# Granny_Safe_Microprocessor_Module.net
KiCad netlist of a schematic drawn in EAGLE
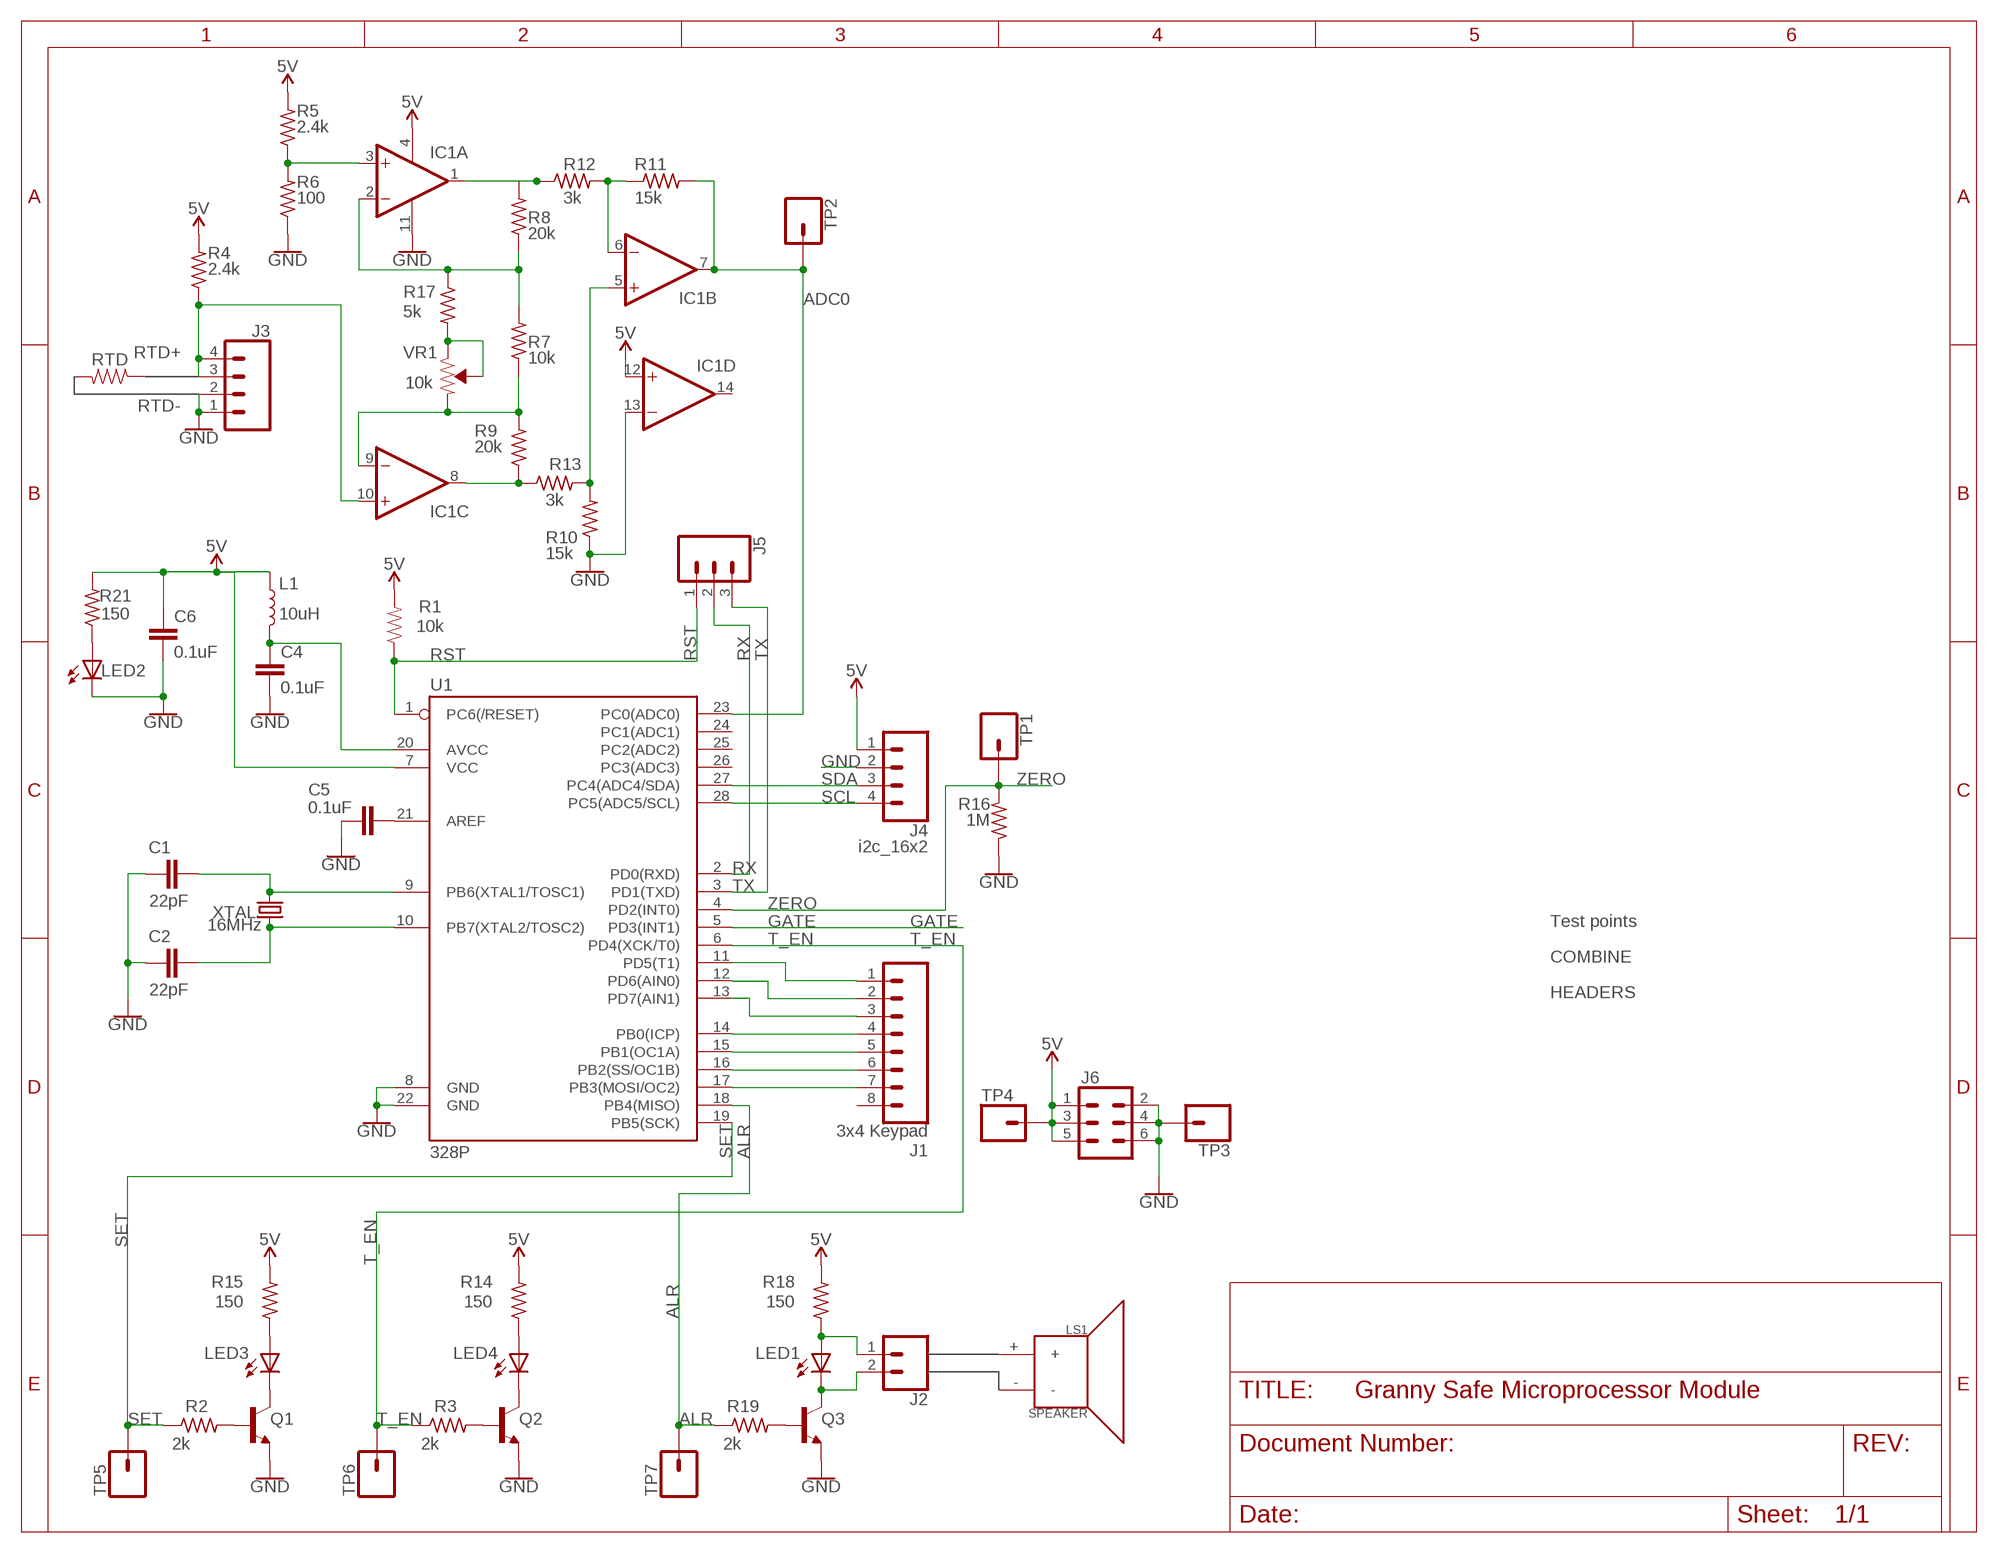
[diagram p0: schematic, sheet 1]

(export (version "E")
  (design (tool "Eeschema 10.0.6"))
  (components
    (comp (ref "C1")
      (value "22pF")
      (footprint "eagle-import:0603")
      (libsource (lib "eagle-import") (part "22PF-0603-50V-5%"))
    )
    (comp (ref "C2")
      (value "22pF")
      (footprint "eagle-import:0603")
      (libsource (lib "eagle-import") (part "22PF-0603-50V-5%"))
    )
    (comp (ref "C4")
      (value "0.1uF")
      (footprint "eagle-import:0603")
      (libsource (lib "eagle-import") (part "0.1UF-0603-25V-(+80/-20%)"))
    )
    (comp (ref "C5")
      (value "0.1uF")
      (footprint "eagle-import:0603")
      (libsource (lib "eagle-import") (part "0.1UF-0603-25V-(+80/-20%)"))
    )
    (comp (ref "C6")
      (value "0.1uF")
      (footprint "eagle-import:0603")
      (libsource (lib "eagle-import") (part "0.1UF-0603-25V-(+80/-20%)"))
    )
    (comp (ref "IC1")
      (value "MCP604SL")
      (footprint "eagle-import:SO14")
      (libsource (lib "eagle-import") (part "MCP604SL"))
    )
    (comp (ref "J1")
      (value "3x4 Keypad")
      (footprint "eagle-import:1X08")
      (libsource (lib "eagle-import") (part "CONN_08{dblquote}"))
    )
    (comp (ref "J2")
      (value "CONN_02")
      (footprint "eagle-import:1X02")
      (libsource (lib "eagle-import") (part "CONN_02"))
    )
    (comp (ref "J3")
      (value "SCREW-4")
      (footprint "eagle-import:SCREWTERMINAL-5MM-2")
      (libsource (lib "eagle-import") (part "SCREW-4"))
    )
    (comp (ref "J4")
      (value "i2c_16x2")
      (footprint "eagle-import:1X04")
      (libsource (lib "eagle-import") (part "CONN_04"))
    )
    (comp (ref "J5")
      (value "CONN_03")
      (footprint "eagle-import:1X03")
      (libsource (lib "eagle-import") (part "CONN_03"))
    )
    (comp (ref "J6")
      (value "FEMALE 2x3")
      (footprint "eagle-import:2X3")
      (libsource (lib "eagle-import") (part "CONN_03X2FEMALE"))
    )
    (comp (ref "L1")
      (value "10uH")
      (footprint "eagle-import:0603")
      (libsource (lib "eagle-import") (part "INDUCTOR-0603-33NH"))
    )
    (comp (ref "LED1")
      (value "LED5MM")
      (footprint "eagle-import:LED5MM")
      (libsource (lib "eagle-import") (part "LED5MM"))
    )
    (comp (ref "LED2")
      (value "LED5MM")
      (footprint "eagle-import:LED5MM")
      (libsource (lib "eagle-import") (part "LED5MM"))
    )
    (comp (ref "LED3")
      (value "LED5MM")
      (footprint "eagle-import:LED5MM")
      (libsource (lib "eagle-import") (part "LED5MM"))
    )
    (comp (ref "LED4")
      (value "LED5MM")
      (footprint "eagle-import:LED5MM")
      (libsource (lib "eagle-import") (part "LED5MM"))
    )
    (comp (ref "LS1")
      (value "SPEAKER")
      (footprint "eagle-import:PCB_MOUNT_SPEAKER")
      (libsource (lib "eagle-import") (part "SPEAKER"))
    )
    (comp (ref "Q1")
      (value "TRANS_NPN-MMBTA42")
      (footprint "eagle-import:SOT23-3")
      (libsource (lib "eagle-import") (part "TRANS_NPN-MMBTA42"))
    )
    (comp (ref "Q2")
      (value "TRANS_NPN-MMBTA42")
      (footprint "eagle-import:SOT23-3")
      (libsource (lib "eagle-import") (part "TRANS_NPN-MMBTA42"))
    )
    (comp (ref "Q3")
      (value "TRANS_NPN-MMBTA42")
      (footprint "eagle-import:SOT23-3")
      (libsource (lib "eagle-import") (part "TRANS_NPN-MMBTA42"))
    )
    (comp (ref "R1")
      (value "10k")
      (footprint "eagle-import:0603")
      (libsource (lib "eagle-import") (part "10KOHM-0603-1/10W-1%"))
    )
    (comp (ref "R2")
      (value "2k")
      (footprint "eagle-import:R0603")
      (libsource (lib "eagle-import") (part "R-US_R0603"))
    )
    (comp (ref "R3")
      (value "2k")
      (footprint "eagle-import:R0603")
      (libsource (lib "eagle-import") (part "R-US_R0603"))
    )
    (comp (ref "R4")
      (value "2.4k")
      (footprint "eagle-import:R0603")
      (libsource (lib "eagle-import") (part "resistor_348_R-US_R0603"))
    )
    (comp (ref "R5")
      (value "2.4k")
      (footprint "eagle-import:R0603")
      (libsource (lib "eagle-import") (part "resistor_348_R-US_R0603"))
    )
    (comp (ref "R6")
      (value "100")
      (footprint "eagle-import:R0603")
      (libsource (lib "eagle-import") (part "resistor_348_R-US_R0603"))
    )
    (comp (ref "R7")
      (value "10k")
      (footprint "eagle-import:R0603")
      (libsource (lib "eagle-import") (part "resistor_348_R-US_R0603"))
    )
    (comp (ref "R8")
      (value "20k")
      (footprint "eagle-import:R0603")
      (libsource (lib "eagle-import") (part "resistor_348_R-US_R0603"))
    )
    (comp (ref "R9")
      (value "20k")
      (footprint "eagle-import:R0603")
      (libsource (lib "eagle-import") (part "resistor_348_R-US_R0603"))
    )
    (comp (ref "R10")
      (value "15k")
      (footprint "eagle-import:R0603")
      (libsource (lib "eagle-import") (part "resistor_348_R-US_R0603"))
    )
    (comp (ref "R11")
      (value "15k")
      (footprint "eagle-import:R0603")
      (libsource (lib "eagle-import") (part "resistor_348_R-US_R0603"))
    )
    (comp (ref "R12")
      (value "3k")
      (footprint "eagle-import:R0603")
      (libsource (lib "eagle-import") (part "resistor_348_R-US_R0603"))
    )
    (comp (ref "R13")
      (value "3k")
      (footprint "eagle-import:R0603")
      (libsource (lib "eagle-import") (part "resistor_348_R-US_R0603"))
    )
    (comp (ref "R14")
      (value "150")
      (footprint "eagle-import:R0603")
      (libsource (lib "eagle-import") (part "R-US_R0603"))
    )
    (comp (ref "R15")
      (value "150")
      (footprint "eagle-import:R0603")
      (libsource (lib "eagle-import") (part "R-US_R0603"))
    )
    (comp (ref "R16")
      (value "1M")
      (footprint "eagle-import:R0603")
      (libsource (lib "eagle-import") (part "resistor_348_R-US_R0603"))
    )
    (comp (ref "R17")
      (value "5k")
      (footprint "eagle-import:R0603")
      (libsource (lib "eagle-import") (part "resistor_348_R-US_R0603"))
    )
    (comp (ref "R18")
      (value "150")
      (footprint "eagle-import:R0603")
      (libsource (lib "eagle-import") (part "R-US_R0603"))
    )
    (comp (ref "R19")
      (value "2k")
      (footprint "eagle-import:R0603")
      (libsource (lib "eagle-import") (part "R-US_R0603"))
    )
    (comp (ref "R21")
      (value "150")
      (footprint "eagle-import:R0603")
      (libsource (lib "eagle-import") (part "R-US_R0603"))
    )
    (comp (ref "RTD")
      (value "10KOHM-HORIZ-1/4W-1%")
      (footprint "eagle-import:AXIAL-0.3")
      (libsource (lib "eagle-import") (part "10KOHM-HORIZ-1/4W-1%"))
    )
    (comp (ref "TP1")
      (value "CONN_01")
      (footprint "eagle-import:1X01")
      (libsource (lib "eagle-import") (part "CONN_01"))
    )
    (comp (ref "TP2")
      (value "CONN_01")
      (footprint "eagle-import:1X01")
      (libsource (lib "eagle-import") (part "CONN_01"))
    )
    (comp (ref "TP3")
      (value "CONN_01")
      (footprint "eagle-import:1X01")
      (libsource (lib "eagle-import") (part "CONN_01"))
    )
    (comp (ref "TP4")
      (value "CONN_01")
      (footprint "eagle-import:1X01")
      (libsource (lib "eagle-import") (part "CONN_01"))
    )
    (comp (ref "TP5")
      (value "CONN_01")
      (footprint "eagle-import:1X01")
      (libsource (lib "eagle-import") (part "CONN_01"))
    )
    (comp (ref "TP6")
      (value "CONN_01")
      (footprint "eagle-import:1X01")
      (libsource (lib "eagle-import") (part "CONN_01"))
    )
    (comp (ref "TP7")
      (value "CONN_01")
      (footprint "eagle-import:1X01")
      (libsource (lib "eagle-import") (part "CONN_01"))
    )
    (comp (ref "U1")
      (value "328P")
      (footprint "eagle-import:DIP28")
      (libsource (lib "eagle-import") (part "ATMEGA328P_PDIP"))
    )
    (comp (ref "VR1")
      (value "10k")
      (footprint "eagle-import:TRIMPOT-SMD-3MM-CLOSED")
      (libsource (lib "eagle-import") (part "TRIMPOT-SMD-3MM-CLOSED-1/8W-20%"))
    )
    (comp (ref "XTAL")
      (value "16MHz")
      (footprint "eagle-import:HC49US")
      (libsource (lib "eagle-import") (part "CRYSTAL-16MHZPTH-HC49US"))
    )
  )
  (nets
    (net (code "1") (name "/ADC0") (class "Default")
      (node (ref "IC1") (pin "7") (pinfunction "OUT_7") (pintype "output"))
      (node (ref "R11") (pin "2") (pinfunction "2_2") (pintype "passive"))
      (node (ref "TP2") (pin "1") (pinfunction "1_1") (pintype "passive"))
      (node (ref "U1") (pin "23") (pinfunction "PC0(ADC0)_23") (pintype "bidirectional"))
    )
    (net (code "2") (name "/ALR") (class "Default")
      (node (ref "R19") (pin "1") (pinfunction "1_1") (pintype "passive"))
      (node (ref "TP7") (pin "1") (pinfunction "1_1") (pintype "passive"))
      (node (ref "U1") (pin "18") (pinfunction "PB4(MISO)_18") (pintype "bidirectional"))
    )
    (net (code "3") (name "/GATE") (class "Default")
      (node (ref "U1") (pin "5") (pinfunction "PD3(INT1)_5") (pintype "bidirectional"))
    )
    (net (code "4") (name "/RST") (class "Default")
      (node (ref "J5") (pin "1") (pinfunction "1_1") (pintype "passive"))
      (node (ref "R1") (pin "1") (pinfunction "1_1") (pintype "passive"))
      (node (ref "U1") (pin "1") (pinfunction "PC6(/RESET)_1") (pintype "bidirectional"))
    )
    (net (code "5") (name "/RX") (class "Default")
      (node (ref "J5") (pin "2") (pinfunction "2_2") (pintype "passive"))
      (node (ref "U1") (pin "2") (pinfunction "PD0(RXD)_2") (pintype "bidirectional"))
    )
    (net (code "6") (name "/SCL") (class "Default")
      (node (ref "J4") (pin "4") (pinfunction "4_4") (pintype "passive"))
      (node (ref "U1") (pin "28") (pinfunction "PC5(ADC5/SCL)_28") (pintype "bidirectional"))
    )
    (net (code "7") (name "/SDA") (class "Default")
      (node (ref "J4") (pin "3") (pinfunction "3_3") (pintype "passive"))
      (node (ref "U1") (pin "27") (pinfunction "PC4(ADC4/SDA)_27") (pintype "bidirectional"))
    )
    (net (code "8") (name "/SET") (class "Default")
      (node (ref "R2") (pin "1") (pinfunction "1_1") (pintype "passive"))
      (node (ref "TP5") (pin "1") (pinfunction "1_1") (pintype "passive"))
      (node (ref "U1") (pin "19") (pinfunction "PB5(SCK)_19") (pintype "bidirectional"))
    )
    (net (code "9") (name "/TX") (class "Default")
      (node (ref "J5") (pin "3") (pinfunction "3_3") (pintype "passive"))
      (node (ref "U1") (pin "3") (pinfunction "PD1(TXD)_3") (pintype "bidirectional"))
    )
    (net (code "10") (name "/T_EN") (class "Default")
      (node (ref "R3") (pin "1") (pinfunction "1_1") (pintype "passive"))
      (node (ref "TP6") (pin "1") (pinfunction "1_1") (pintype "passive"))
      (node (ref "U1") (pin "6") (pinfunction "PD4(XCK/T0)_6") (pintype "bidirectional"))
    )
    (net (code "11") (name "/ZERO") (class "Default")
      (node (ref "R16") (pin "2") (pinfunction "2_2") (pintype "passive"))
      (node (ref "TP1") (pin "1") (pinfunction "1_1") (pintype "passive"))
      (node (ref "U1") (pin "4") (pinfunction "PD2(INT0)_4") (pintype "bidirectional"))
    )
    (net (code "12") (name "5V") (class "Default")
      (node (ref "C6") (pin "1") (pinfunction "1_1") (pintype "passive"))
      (node (ref "IC1") (pin "12") (pinfunction "+IN_12") (pintype "input"))
      (node (ref "IC1") (pin "4") (pinfunction "V+_4") (pintype "power_in"))
      (node (ref "J4") (pin "1") (pinfunction "1_1") (pintype "passive"))
      (node (ref "J6") (pin "1") (pinfunction "1_1") (pintype "bidirectional"))
      (node (ref "J6") (pin "3") (pinfunction "3_3") (pintype "bidirectional"))
      (node (ref "J6") (pin "5") (pinfunction "5_5") (pintype "bidirectional"))
      (node (ref "L1") (pin "1") (pinfunction "1_1") (pintype "passive"))
      (node (ref "R1") (pin "2") (pinfunction "2_2") (pintype "passive"))
      (node (ref "R14") (pin "2") (pinfunction "2_2") (pintype "passive"))
      (node (ref "R15") (pin "2") (pinfunction "2_2") (pintype "passive"))
      (node (ref "R18") (pin "2") (pinfunction "2_2") (pintype "passive"))
      (node (ref "R21") (pin "2") (pinfunction "2_2") (pintype "passive"))
      (node (ref "R4") (pin "2") (pinfunction "2_2") (pintype "passive"))
      (node (ref "R5") (pin "2") (pinfunction "2_2") (pintype "passive"))
      (node (ref "TP4") (pin "1") (pinfunction "1_1") (pintype "passive"))
      (node (ref "U1") (pin "7") (pinfunction "VCC_7") (pintype "bidirectional"))
    )
    (net (code "13") (name "GND") (class "Default")
      (node (ref "C1") (pin "1") (pinfunction "1_1") (pintype "passive"))
      (node (ref "C2") (pin "1") (pinfunction "1_1") (pintype "passive"))
      (node (ref "C4") (pin "2") (pinfunction "2_2") (pintype "passive"))
      (node (ref "C5") (pin "2") (pinfunction "2_2") (pintype "passive"))
      (node (ref "C6") (pin "2") (pinfunction "2_2") (pintype "passive"))
      (node (ref "IC1") (pin "11") (pinfunction "V-_11") (pintype "power_in"))
      (node (ref "IC1") (pin "13") (pinfunction "-IN_13") (pintype "input"))
      (node (ref "J3") (pin "1") (pinfunction "1_1") (pintype "passive"))
      (node (ref "J3") (pin "2") (pinfunction "2_2") (pintype "passive"))
      (node (ref "J4") (pin "2") (pinfunction "2_2") (pintype "passive"))
      (node (ref "J6") (pin "2") (pinfunction "2_2") (pintype "bidirectional"))
      (node (ref "J6") (pin "4") (pinfunction "4_4") (pintype "bidirectional"))
      (node (ref "J6") (pin "6") (pinfunction "6_6") (pintype "bidirectional"))
      (node (ref "LED2") (pin "K") (pinfunction "C_K") (pintype "passive"))
      (node (ref "Q1") (pin "2") (pinfunction "E_2") (pintype "passive"))
      (node (ref "Q2") (pin "2") (pinfunction "E_2") (pintype "passive"))
      (node (ref "Q3") (pin "2") (pinfunction "E_2") (pintype "passive"))
      (node (ref "R10") (pin "1") (pinfunction "1_1") (pintype "passive"))
      (node (ref "R16") (pin "1") (pinfunction "1_1") (pintype "passive"))
      (node (ref "R6") (pin "1") (pinfunction "1_1") (pintype "passive"))
      (node (ref "TP3") (pin "1") (pinfunction "1_1") (pintype "passive"))
      (node (ref "U1") (pin "22") (pinfunction "GND_22") (pintype "bidirectional"))
      (node (ref "U1") (pin "8") (pinfunction "GND_8") (pintype "bidirectional"))
    )
    (net (code "14") (name "Net-(IC1A-+IN)") (class "Default")
      (node (ref "IC1") (pin "3") (pinfunction "+IN_3") (pintype "input"))
      (node (ref "R5") (pin "1") (pinfunction "1_1") (pintype "passive"))
      (node (ref "R6") (pin "2") (pinfunction "2_2") (pintype "passive"))
    )
    (net (code "15") (name "Net-(IC1A--IN)") (class "Default")
      (node (ref "IC1") (pin "2") (pinfunction "-IN_2") (pintype "input"))
      (node (ref "R17") (pin "1") (pinfunction "1_1") (pintype "passive"))
      (node (ref "R7") (pin "2") (pinfunction "2_2") (pintype "passive"))
      (node (ref "R8") (pin "1") (pinfunction "1_1") (pintype "passive"))
    )
    (net (code "16") (name "Net-(IC1A-OUT)") (class "Default")
      (node (ref "IC1") (pin "1") (pinfunction "OUT_1") (pintype "output"))
      (node (ref "R12") (pin "1") (pinfunction "1_1") (pintype "passive"))
      (node (ref "R8") (pin "2") (pinfunction "2_2") (pintype "passive"))
    )
    (net (code "17") (name "Net-(IC1B-+IN)") (class "Default")
      (node (ref "IC1") (pin "5") (pinfunction "+IN_5") (pintype "input"))
      (node (ref "R10") (pin "2") (pinfunction "2_2") (pintype "passive"))
      (node (ref "R13") (pin "2") (pinfunction "2_2") (pintype "passive"))
    )
    (net (code "18") (name "Net-(IC1B--IN)") (class "Default")
      (node (ref "IC1") (pin "6") (pinfunction "-IN_6") (pintype "input"))
      (node (ref "R11") (pin "1") (pinfunction "1_1") (pintype "passive"))
      (node (ref "R12") (pin "2") (pinfunction "2_2") (pintype "passive"))
    )
    (net (code "19") (name "Net-(IC1C-+IN)") (class "Default")
      (node (ref "IC1") (pin "10") (pinfunction "+IN_10") (pintype "input"))
      (node (ref "J3") (pin "3") (pinfunction "3_3") (pintype "passive"))
      (node (ref "J3") (pin "4") (pinfunction "4_4") (pintype "passive"))
      (node (ref "R4") (pin "1") (pinfunction "1_1") (pintype "passive"))
    )
    (net (code "20") (name "Net-(IC1C--IN)") (class "Default")
      (node (ref "IC1") (pin "9") (pinfunction "-IN_9") (pintype "input"))
      (node (ref "R7") (pin "1") (pinfunction "1_1") (pintype "passive"))
      (node (ref "R9") (pin "2") (pinfunction "2_2") (pintype "passive"))
      (node (ref "VR1") (pin "1") (pinfunction "CCW_1") (pintype "passive"))
    )
    (net (code "21") (name "Net-(IC1C-OUT)") (class "Default")
      (node (ref "IC1") (pin "8") (pinfunction "OUT_8") (pintype "output"))
      (node (ref "R13") (pin "1") (pinfunction "1_1") (pintype "passive"))
      (node (ref "R9") (pin "1") (pinfunction "1_1") (pintype "passive"))
    )
    (net (code "22") (name "Net-(J2-Pad1)") (class "Default")
      (node (ref "J2") (pin "1") (pinfunction "1_1") (pintype "passive"))
      (node (ref "LED1") (pin "A") (pinfunction "A_A") (pintype "passive"))
      (node (ref "R18") (pin "1") (pinfunction "1_1") (pintype "passive"))
    )
    (net (code "23") (name "Net-(LED1-C)") (class "Default")
      (node (ref "J2") (pin "2") (pinfunction "2_2") (pintype "passive"))
      (node (ref "LED1") (pin "K") (pinfunction "C_K") (pintype "passive"))
      (node (ref "Q3") (pin "3") (pinfunction "C_3") (pintype "passive"))
    )
    (net (code "24") (name "Net-(LED2-PadA)") (class "Default")
      (node (ref "LED2") (pin "A") (pinfunction "A_A") (pintype "passive"))
      (node (ref "R21") (pin "1") (pinfunction "1_1") (pintype "passive"))
    )
    (net (code "25") (name "Net-(LED3-C)") (class "Default")
      (node (ref "LED3") (pin "K") (pinfunction "C_K") (pintype "passive"))
      (node (ref "Q1") (pin "3") (pinfunction "C_3") (pintype "passive"))
    )
    (net (code "26") (name "Net-(LED3-PadA)") (class "Default")
      (node (ref "LED3") (pin "A") (pinfunction "A_A") (pintype "passive"))
      (node (ref "R15") (pin "1") (pinfunction "1_1") (pintype "passive"))
    )
    (net (code "27") (name "Net-(LED4-C)") (class "Default")
      (node (ref "LED4") (pin "K") (pinfunction "C_K") (pintype "passive"))
      (node (ref "Q2") (pin "3") (pinfunction "C_3") (pintype "passive"))
    )
    (net (code "28") (name "Net-(LED4-PadA)") (class "Default")
      (node (ref "LED4") (pin "A") (pinfunction "A_A") (pintype "passive"))
      (node (ref "R14") (pin "1") (pinfunction "1_1") (pintype "passive"))
    )
    (net (code "29") (name "Net-(Q1-B)") (class "Default")
      (node (ref "Q1") (pin "1") (pinfunction "B_1") (pintype "passive"))
      (node (ref "R2") (pin "2") (pinfunction "2_2") (pintype "passive"))
    )
    (net (code "30") (name "Net-(Q2-B)") (class "Default")
      (node (ref "Q2") (pin "1") (pinfunction "B_1") (pintype "passive"))
      (node (ref "R3") (pin "2") (pinfunction "2_2") (pintype "passive"))
    )
    (net (code "31") (name "Net-(Q3-B)") (class "Default")
      (node (ref "Q3") (pin "1") (pinfunction "B_1") (pintype "passive"))
      (node (ref "R19") (pin "2") (pinfunction "2_2") (pintype "passive"))
    )
    (net (code "32") (name "Net-(U1-AREF)") (class "Default")
      (node (ref "C5") (pin "1") (pinfunction "1_1") (pintype "passive"))
      (node (ref "U1") (pin "21") (pinfunction "AREF_21") (pintype "bidirectional"))
    )
    (net (code "33") (name "Net-(U1-AVCC)") (class "Default")
      (node (ref "C4") (pin "1") (pinfunction "1_1") (pintype "passive"))
      (node (ref "L1") (pin "2") (pinfunction "2_2") (pintype "passive"))
      (node (ref "U1") (pin "20") (pinfunction "AVCC_20") (pintype "bidirectional"))
    )
    (net (code "34") (name "Net-(U1-PB0(ICP))") (class "Default")
      (node (ref "J1") (pin "4") (pinfunction "4_4") (pintype "passive"))
      (node (ref "U1") (pin "14") (pinfunction "PB0(ICP)_14") (pintype "bidirectional"))
    )
    (net (code "35") (name "Net-(U1-PB1(OC1A))") (class "Default")
      (node (ref "J1") (pin "5") (pinfunction "5_5") (pintype "passive"))
      (node (ref "U1") (pin "15") (pinfunction "PB1(OC1A)_15") (pintype "bidirectional"))
    )
    (net (code "36") (name "Net-(U1-PB2(SS{slash}OC1B))") (class "Default")
      (node (ref "J1") (pin "6") (pinfunction "6_6") (pintype "passive"))
      (node (ref "U1") (pin "16") (pinfunction "PB2(SS/OC1B)_16") (pintype "bidirectional"))
    )
    (net (code "37") (name "Net-(U1-PB3(MOSI{slash}OC2))") (class "Default")
      (node (ref "J1") (pin "7") (pinfunction "7_7") (pintype "passive"))
      (node (ref "U1") (pin "17") (pinfunction "PB3(MOSI/OC2)_17") (pintype "bidirectional"))
    )
    (net (code "38") (name "Net-(U1-PB6(XTAL1{slash}TOSC1))") (class "Default")
      (node (ref "C1") (pin "2") (pinfunction "2_2") (pintype "passive"))
      (node (ref "U1") (pin "9") (pinfunction "PB6(XTAL1/TOSC1)_9") (pintype "bidirectional"))
      (node (ref "XTAL") (pin "2") (pinfunction "2_2") (pintype "passive"))
    )
    (net (code "39") (name "Net-(U1-PB7(XTAL2{slash}TOSC2))") (class "Default")
      (node (ref "C2") (pin "2") (pinfunction "2_2") (pintype "passive"))
      (node (ref "U1") (pin "10") (pinfunction "PB7(XTAL2/TOSC2)_10") (pintype "bidirectional"))
      (node (ref "XTAL") (pin "1") (pinfunction "1_1") (pintype "passive"))
    )
    (net (code "40") (name "Net-(U1-PD5(T1))") (class "Default")
      (node (ref "J1") (pin "1") (pinfunction "1_1") (pintype "passive"))
      (node (ref "U1") (pin "11") (pinfunction "PD5(T1)_11") (pintype "bidirectional"))
    )
    (net (code "41") (name "Net-(U1-PD6(AIN0))") (class "Default")
      (node (ref "J1") (pin "2") (pinfunction "2_2") (pintype "passive"))
      (node (ref "U1") (pin "12") (pinfunction "PD6(AIN0)_12") (pintype "bidirectional"))
    )
    (net (code "42") (name "Net-(U1-PD7(AIN1))") (class "Default")
      (node (ref "J1") (pin "3") (pinfunction "3_3") (pintype "passive"))
      (node (ref "U1") (pin "13") (pinfunction "PD7(AIN1)_13") (pintype "bidirectional"))
    )
    (net (code "43") (name "Net-(VR1-CW)") (class "Default")
      (node (ref "R17") (pin "2") (pinfunction "2_2") (pintype "passive"))
      (node (ref "VR1") (pin "2") (pinfunction "WIPER_2") (pintype "passive"))
      (node (ref "VR1") (pin "3") (pinfunction "CW_3") (pintype "passive"))
    )
    (net (code "44") (name "unconnected-(IC1D-OUT-Pad14)") (class "Default")
      (node (ref "IC1") (pin "14") (pinfunction "OUT_14") (pintype "output"))
    )
    (net (code "45") (name "unconnected-(J1-Pad8)") (class "Default")
      (node (ref "J1") (pin "8") (pinfunction "8_8") (pintype "passive"))
    )
    (net (code "46") (name "unconnected-(LS1-Pad+)") (class "Default")
      (node (ref "LS1") (pin "+") (pinfunction "+_+") (pintype "bidirectional"))
    )
    (net (code "47") (name "unconnected-(LS1-Pad-)") (class "Default")
      (node (ref "LS1") (pin "-") (pinfunction "-_-") (pintype "bidirectional"))
    )
    (net (code "48") (name "unconnected-(RTD-1-PadP$1)") (class "Default")
      (node (ref "RTD") (pin "P$1") (pinfunction "1_P$1") (pintype "passive"))
    )
    (net (code "49") (name "unconnected-(RTD-2-PadP$2)") (class "Default")
      (node (ref "RTD") (pin "P$2") (pinfunction "2_P$2") (pintype "passive"))
    )
    (net (code "50") (name "unconnected-(U1-PC1(ADC1)-Pad24)") (class "Default")
      (node (ref "U1") (pin "24") (pinfunction "PC1(ADC1)_24") (pintype "bidirectional"))
    )
    (net (code "51") (name "unconnected-(U1-PC2(ADC2)-Pad25)") (class "Default")
      (node (ref "U1") (pin "25") (pinfunction "PC2(ADC2)_25") (pintype "bidirectional"))
    )
    (net (code "52") (name "unconnected-(U1-PC3(ADC3)-Pad26)") (class "Default")
      (node (ref "U1") (pin "26") (pinfunction "PC3(ADC3)_26") (pintype "bidirectional"))
    )
  )
)
